# Car_cover_Main1.net
KiCad netlist of a schematic drawn in EAGLE
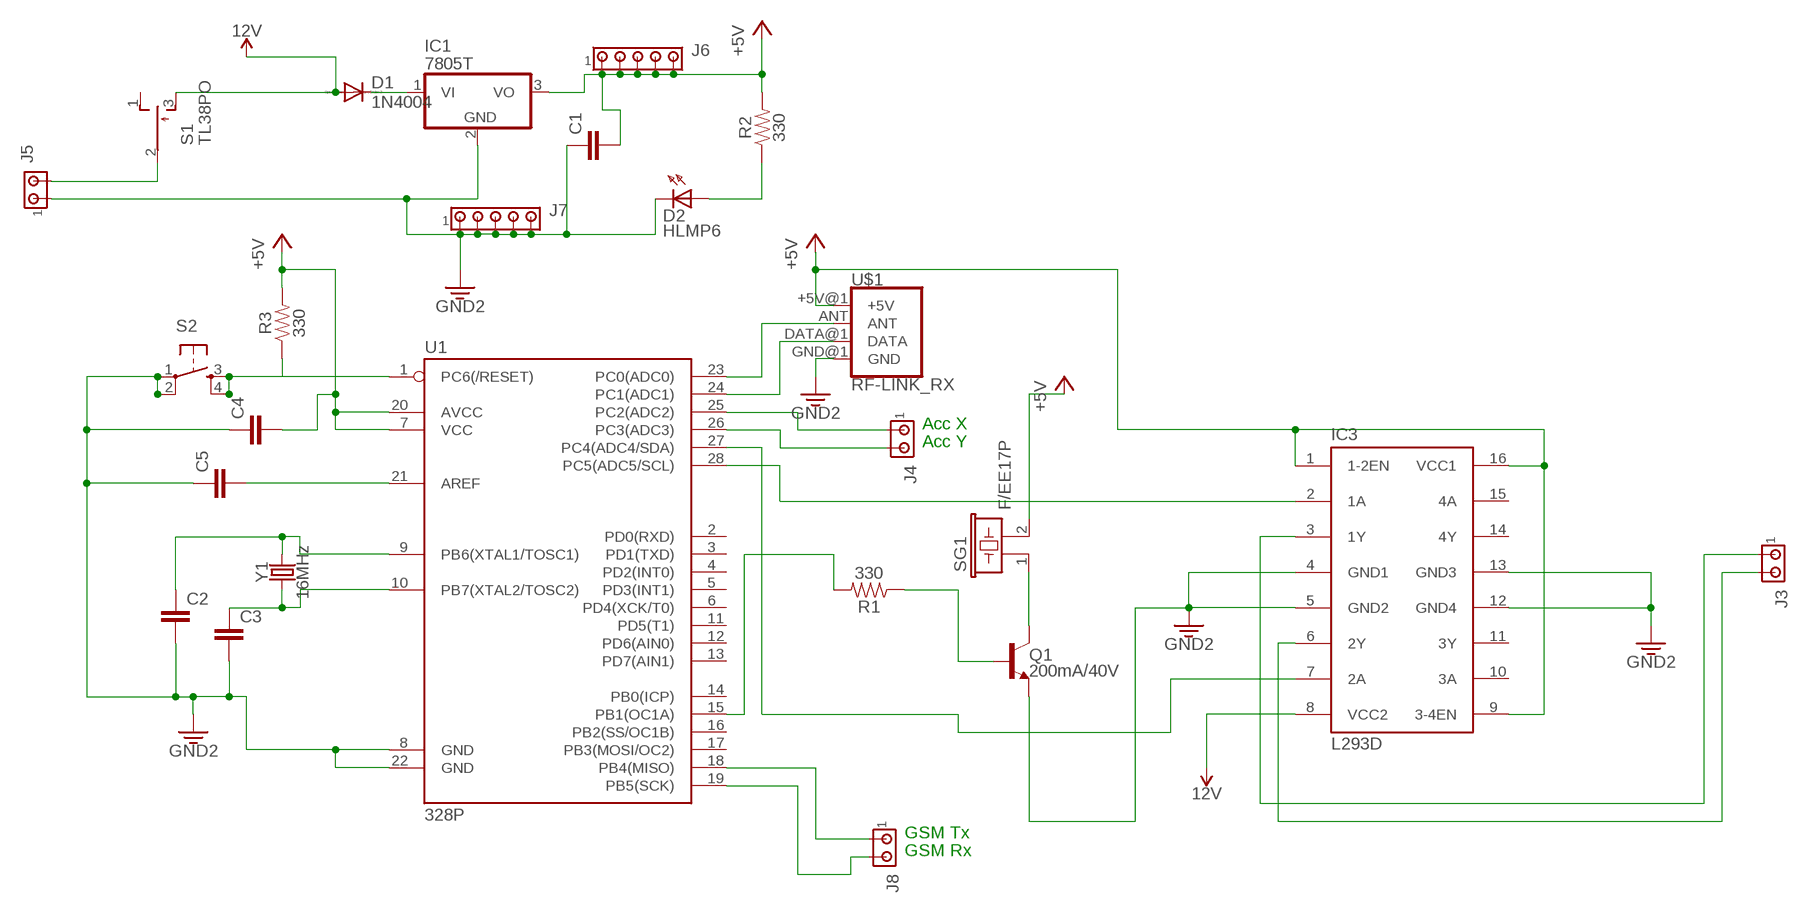
[diagram p0: schematic, sheet 1]

(export (version "E")
  (design (tool "Eeschema 10.0.6"))
  (components
    (comp (ref "C1")
      (value "C5/2.5")
      (footprint "eagle-import:C5B2.5")
      (libsource (lib "eagle-import") (part "C5/2.5"))
    )
    (comp (ref "C2")
      (value "C5/2.5")
      (footprint "eagle-import:C5B2.5")
      (libsource (lib "eagle-import") (part "C5/2.5"))
    )
    (comp (ref "C3")
      (value "C5/2.5")
      (footprint "eagle-import:C5B2.5")
      (libsource (lib "eagle-import") (part "C5/2.5"))
    )
    (comp (ref "C4")
      (value "C5/2.5")
      (footprint "eagle-import:C5B2.5")
      (libsource (lib "eagle-import") (part "C5/2.5"))
    )
    (comp (ref "C5")
      (value "C5/2.5")
      (footprint "eagle-import:C5B2.5")
      (libsource (lib "eagle-import") (part "C5/2.5"))
    )
    (comp (ref "D1")
      (value "1N4004")
      (footprint "eagle-import:DO41-10")
      (libsource (lib "eagle-import") (part "1N4004"))
    )
    (comp (ref "D2")
      (value "HLMP6")
      (footprint "eagle-import:HLMP6")
      (fields (field (name "MF") "AGILENT TECHNOLOGIES") (field (name "MPN") "HLMP-6500"))
      (libsource (lib "eagle-import") (part "HLMP6"))
    )
    (comp (ref "IC1")
      (value "7805T")
      (footprint "eagle-import:TO220H")
      (libsource (lib "eagle-import") (part "78T05"))
    )
    (comp (ref "IC3")
      (value "L293D")
      (footprint "eagle-import:DIL16")
      (libsource (lib "eagle-import") (part "L293D"))
    )
    (comp (ref "J3")
      (value "MTA02-156")
      (footprint "eagle-import:1X2MTA")
      (libsource (lib "eagle-import") (part "MTA02-156"))
    )
    (comp (ref "J4")
      (value "MTA02-156")
      (footprint "eagle-import:1X2MTA")
      (libsource (lib "eagle-import") (part "MTA02-156"))
    )
    (comp (ref "J5")
      (value "MTA02-156")
      (footprint "eagle-import:1X2MTA")
      (libsource (lib "eagle-import") (part "MTA02-156"))
    )
    (comp (ref "J6")
      (value "MTA05-100")
      (footprint "eagle-import:10X05MTA")
      (libsource (lib "eagle-import") (part "MTA05-100"))
    )
    (comp (ref "J7")
      (value "MTA05-100")
      (footprint "eagle-import:10X05MTA")
      (libsource (lib "eagle-import") (part "MTA05-100"))
    )
    (comp (ref "J8")
      (value "MTA02-156")
      (footprint "eagle-import:1X2MTA")
      (libsource (lib "eagle-import") (part "MTA02-156"))
    )
    (comp (ref "Q1")
      (value "200mA/40V")
      (footprint "eagle-import:TO-92")
      (libsource (lib "eagle-import") (part "TRANS_NPN-2N3904"))
    )
    (comp (ref "R1")
      (value "330")
      (footprint "eagle-import:AXIAL-0.3")
      (libsource (lib "eagle-import") (part "330OHM-HORIZ-1/10W-5%"))
    )
    (comp (ref "R2")
      (value "330")
      (footprint "eagle-import:AXIAL-0.3")
      (libsource (lib "eagle-import") (part "330OHM-HORIZ-1/10W-5%"))
    )
    (comp (ref "R3")
      (value "330")
      (footprint "eagle-import:AXIAL-0.3")
      (libsource (lib "eagle-import") (part "330OHM-HORIZ-1/10W-5%"))
    )
    (comp (ref "S1")
      (value "TL38PO")
      (footprint "eagle-import:TL3XPO")
      (libsource (lib "eagle-import") (part "TL38PO"))
    )
    (comp (ref "S2")
      (value "TAC_SWITCHPTH")
      (footprint "eagle-import:TACTILE-PTH")
      (libsource (lib "eagle-import") (part "TAC_SWITCHPTH"))
    )
    (comp (ref "SG1")
      (value "F/EE17P")
      (footprint "eagle-import:F_EE17P")
      (libsource (lib "eagle-import") (part "F/EE17P"))
    )
    (comp (ref "U$1")
      (value "RF-LINK_RX")
      (footprint "eagle-import:RF-LINK_RX")
      (libsource (lib "eagle-import") (part "RF-LINK_RX"))
    )
    (comp (ref "U1")
      (value "328P")
      (footprint "eagle-import:DIP28")
      (libsource (lib "eagle-import") (part "ATMEGA328P_PDIP"))
    )
    (comp (ref "Y1")
      (value "16MHz")
      (footprint "eagle-import:HC49US")
      (libsource (lib "eagle-import") (part "CRYSTAL-16MHZPTH-HC49US"))
    )
  )
  (nets
    (net (code "1") (name "+5V") (class "Default")
      (node (ref "C1") (pin "2") (pinfunction "2_2") (pintype "passive"))
      (node (ref "C4") (pin "2") (pinfunction "2_2") (pintype "passive"))
      (node (ref "IC1") (pin "3") (pinfunction "VO_3") (pintype "passive"))
      (node (ref "IC3") (pin "1") (pinfunction "1-2EN_1") (pintype "input"))
      (node (ref "IC3") (pin "16") (pinfunction "VCC1_16") (pintype "power_in"))
      (node (ref "IC3") (pin "9") (pinfunction "3-4EN_9") (pintype "input"))
      (node (ref "J6") (pin "1") (pinfunction "1_1") (pintype "passive"))
      (node (ref "J6") (pin "2") (pinfunction "2_2") (pintype "passive"))
      (node (ref "J6") (pin "3") (pinfunction "3_3") (pintype "passive"))
      (node (ref "J6") (pin "4") (pinfunction "4_4") (pintype "passive"))
      (node (ref "J6") (pin "5") (pinfunction "5_5") (pintype "passive"))
      (node (ref "R2") (pin "P$2") (pinfunction "2_P$2") (pintype "passive"))
      (node (ref "R3") (pin "P$2") (pinfunction "2_P$2") (pintype "passive"))
      (node (ref "SG1") (pin "2") (pinfunction "2_2") (pintype "passive"))
      (node (ref "U$1") (pin "+5V@1") (pinfunction "+5V_+5V@1") (pintype "power_in"))
      (node (ref "U1") (pin "20") (pinfunction "AVCC_20") (pintype "bidirectional"))
      (node (ref "U1") (pin "7") (pinfunction "VCC_7") (pintype "bidirectional"))
    )
    (net (code "2") (name "12V") (class "Default")
      (node (ref "D1") (pin "A") (pinfunction "A_A") (pintype "passive"))
      (node (ref "IC3") (pin "8") (pinfunction "VCC2_8") (pintype "power_in"))
      (node (ref "S1") (pin "3") (pinfunction "S_3") (pintype "passive"))
    )
    (net (code "3") (name "GND2") (class "Default")
      (node (ref "C1") (pin "1") (pinfunction "1_1") (pintype "passive"))
      (node (ref "C2") (pin "2") (pinfunction "2_2") (pintype "passive"))
      (node (ref "C3") (pin "2") (pinfunction "2_2") (pintype "passive"))
      (node (ref "C4") (pin "1") (pinfunction "1_1") (pintype "passive"))
      (node (ref "C5") (pin "1") (pinfunction "1_1") (pintype "passive"))
      (node (ref "D2") (pin "K") (pinfunction "K_K") (pintype "passive"))
      (node (ref "IC1") (pin "2") (pinfunction "GND_2") (pintype "passive"))
      (node (ref "IC3") (pin "12") (pinfunction "GND4_12") (pintype "power_in"))
      (node (ref "IC3") (pin "13") (pinfunction "GND3_13") (pintype "power_in"))
      (node (ref "IC3") (pin "4") (pinfunction "GND1_4") (pintype "power_in"))
      (node (ref "IC3") (pin "5") (pinfunction "GND2_5") (pintype "power_in"))
      (node (ref "J5") (pin "1") (pinfunction "1_1") (pintype "passive"))
      (node (ref "J7") (pin "1") (pinfunction "1_1") (pintype "passive"))
      (node (ref "J7") (pin "2") (pinfunction "2_2") (pintype "passive"))
      (node (ref "J7") (pin "3") (pinfunction "3_3") (pintype "passive"))
      (node (ref "J7") (pin "4") (pinfunction "4_4") (pintype "passive"))
      (node (ref "J7") (pin "5") (pinfunction "5_5") (pintype "passive"))
      (node (ref "Q1") (pin "1") (pinfunction "E_1") (pintype "passive"))
      (node (ref "S2") (pin "1") (pinfunction "1_1") (pintype "passive"))
      (node (ref "S2") (pin "2") (pinfunction "2_2") (pintype "passive"))
      (node (ref "U$1") (pin "GND@1") (pinfunction "GND_GND@1") (pintype "power_in"))
      (node (ref "U1") (pin "22") (pinfunction "GND_22") (pintype "bidirectional"))
      (node (ref "U1") (pin "8") (pinfunction "GND_8") (pintype "bidirectional"))
    )
    (net (code "4") (name "Net-(IC1-VI)") (class "Default")
      (node (ref "D1") (pin "C") (pinfunction "C_C") (pintype "passive"))
      (node (ref "IC1") (pin "1") (pinfunction "VI_1") (pintype "input"))
    )
    (net (code "5") (name "Net-(IC3-1A)") (class "Default")
      (node (ref "IC3") (pin "2") (pinfunction "1A_2") (pintype "input"))
      (node (ref "U1") (pin "28") (pinfunction "PC5(ADC5/SCL)_28") (pintype "bidirectional"))
    )
    (net (code "6") (name "Net-(IC3-1Y)") (class "Default")
      (node (ref "IC3") (pin "3") (pinfunction "1Y_3") (pintype "output"))
      (node (ref "J3") (pin "1") (pinfunction "1_1") (pintype "passive"))
    )
    (net (code "7") (name "Net-(IC3-2A)") (class "Default")
      (node (ref "IC3") (pin "7") (pinfunction "2A_7") (pintype "input"))
      (node (ref "U1") (pin "27") (pinfunction "PC4(ADC4/SDA)_27") (pintype "bidirectional"))
    )
    (net (code "8") (name "Net-(IC3-2Y)") (class "Default")
      (node (ref "IC3") (pin "6") (pinfunction "2Y_6") (pintype "output"))
      (node (ref "J3") (pin "2") (pinfunction "2_2") (pintype "passive"))
    )
    (net (code "9") (name "Net-(Q1-B)") (class "Default")
      (node (ref "Q1") (pin "2") (pinfunction "B_2") (pintype "passive"))
      (node (ref "R1") (pin "P$1") (pinfunction "1_P$1") (pintype "passive"))
    )
    (net (code "10") (name "Net-(Q1-C)") (class "Default")
      (node (ref "Q1") (pin "3") (pinfunction "C_3") (pintype "passive"))
      (node (ref "SG1") (pin "1") (pinfunction "1_1") (pintype "passive"))
    )
    (net (code "11") (name "Net-(R1-2)") (class "Default")
      (node (ref "R1") (pin "P$2") (pinfunction "2_P$2") (pintype "passive"))
      (node (ref "U1") (pin "15") (pinfunction "PB1(OC1A)_15") (pintype "bidirectional"))
    )
    (net (code "12") (name "Net-(R2-1)") (class "Default")
      (node (ref "D2") (pin "A") (pinfunction "A_A") (pintype "passive"))
      (node (ref "R2") (pin "P$1") (pinfunction "1_P$1") (pintype "passive"))
    )
    (net (code "13") (name "Net-(R3-1)") (class "Default")
      (node (ref "R3") (pin "P$1") (pinfunction "1_P$1") (pintype "passive"))
      (node (ref "S2") (pin "3") (pinfunction "3_3") (pintype "passive"))
      (node (ref "S2") (pin "4") (pinfunction "4_4") (pintype "passive"))
      (node (ref "U1") (pin "1") (pinfunction "PC6(/RESET)_1") (pintype "bidirectional"))
    )
    (net (code "14") (name "Net-(S1-P)") (class "Default")
      (node (ref "J5") (pin "2") (pinfunction "2_2") (pintype "passive"))
      (node (ref "S1") (pin "2") (pinfunction "P_2") (pintype "passive"))
    )
    (net (code "15") (name "Net-(U$1-DATA)") (class "Default")
      (node (ref "U$1") (pin "DATA@1") (pinfunction "DATA_DATA@1") (pintype "input"))
      (node (ref "U1") (pin "24") (pinfunction "PC1(ADC1)_24") (pintype "bidirectional"))
    )
    (net (code "16") (name "Net-(U1-AREF)") (class "Default")
      (node (ref "C5") (pin "2") (pinfunction "2_2") (pintype "passive"))
      (node (ref "U1") (pin "21") (pinfunction "AREF_21") (pintype "bidirectional"))
    )
    (net (code "17") (name "Net-(U1-PB4(MISO))") (class "Default")
      (node (ref "J8") (pin "1") (pinfunction "1_1") (pintype "passive"))
      (node (ref "U1") (pin "18") (pinfunction "PB4(MISO)_18") (pintype "bidirectional"))
    )
    (net (code "18") (name "Net-(U1-PB5(SCK))") (class "Default")
      (node (ref "J8") (pin "2") (pinfunction "2_2") (pintype "passive"))
      (node (ref "U1") (pin "19") (pinfunction "PB5(SCK)_19") (pintype "bidirectional"))
    )
    (net (code "19") (name "Net-(U1-PB6(XTAL1{slash}TOSC1))") (class "Default")
      (node (ref "C2") (pin "1") (pinfunction "1_1") (pintype "passive"))
      (node (ref "U1") (pin "9") (pinfunction "PB6(XTAL1/TOSC1)_9") (pintype "bidirectional"))
      (node (ref "Y1") (pin "2") (pinfunction "2_2") (pintype "passive"))
    )
    (net (code "20") (name "Net-(U1-PB7(XTAL2{slash}TOSC2))") (class "Default")
      (node (ref "C3") (pin "1") (pinfunction "1_1") (pintype "passive"))
      (node (ref "U1") (pin "10") (pinfunction "PB7(XTAL2/TOSC2)_10") (pintype "bidirectional"))
      (node (ref "Y1") (pin "1") (pinfunction "1_1") (pintype "passive"))
    )
    (net (code "21") (name "Net-(U1-PC0(ADC0))") (class "Default")
      (node (ref "U$1") (pin "ANT") (pinfunction "ANT_ANT") (pintype "passive"))
      (node (ref "U1") (pin "23") (pinfunction "PC0(ADC0)_23") (pintype "bidirectional"))
    )
    (net (code "22") (name "Net-(U1-PC2(ADC2))") (class "Default")
      (node (ref "J4") (pin "1") (pinfunction "1_1") (pintype "passive"))
      (node (ref "U1") (pin "25") (pinfunction "PC2(ADC2)_25") (pintype "bidirectional"))
    )
    (net (code "23") (name "Net-(U1-PC3(ADC3))") (class "Default")
      (node (ref "J4") (pin "2") (pinfunction "2_2") (pintype "passive"))
      (node (ref "U1") (pin "26") (pinfunction "PC3(ADC3)_26") (pintype "bidirectional"))
    )
    (net (code "24") (name "unconnected-(IC3-3A-Pad10)") (class "Default")
      (node (ref "IC3") (pin "10") (pinfunction "3A_10") (pintype "input"))
    )
    (net (code "25") (name "unconnected-(IC3-3Y-Pad11)") (class "Default")
      (node (ref "IC3") (pin "11") (pinfunction "3Y_11") (pintype "output"))
    )
    (net (code "26") (name "unconnected-(IC3-4A-Pad15)") (class "Default")
      (node (ref "IC3") (pin "15") (pinfunction "4A_15") (pintype "input"))
    )
    (net (code "27") (name "unconnected-(IC3-4Y-Pad14)") (class "Default")
      (node (ref "IC3") (pin "14") (pinfunction "4Y_14") (pintype "output"))
    )
    (net (code "28") (name "unconnected-(S1-O-Pad1)") (class "Default")
      (node (ref "S1") (pin "1") (pinfunction "O_1") (pintype "passive"))
    )
    (net (code "29") (name "unconnected-(U1-PB0(ICP)-Pad14)") (class "Default")
      (node (ref "U1") (pin "14") (pinfunction "PB0(ICP)_14") (pintype "bidirectional"))
    )
    (net (code "30") (name "unconnected-(U1-PB2(SS{slash}OC1B)-Pad16)") (class "Default")
      (node (ref "U1") (pin "16") (pinfunction "PB2(SS/OC1B)_16") (pintype "bidirectional"))
    )
    (net (code "31") (name "unconnected-(U1-PB3(MOSI{slash}OC2)-Pad17)") (class "Default")
      (node (ref "U1") (pin "17") (pinfunction "PB3(MOSI/OC2)_17") (pintype "bidirectional"))
    )
    (net (code "32") (name "unconnected-(U1-PD0(RXD)-Pad2)") (class "Default")
      (node (ref "U1") (pin "2") (pinfunction "PD0(RXD)_2") (pintype "bidirectional"))
    )
    (net (code "33") (name "unconnected-(U1-PD1(TXD)-Pad3)") (class "Default")
      (node (ref "U1") (pin "3") (pinfunction "PD1(TXD)_3") (pintype "bidirectional"))
    )
    (net (code "34") (name "unconnected-(U1-PD2(INT0)-Pad4)") (class "Default")
      (node (ref "U1") (pin "4") (pinfunction "PD2(INT0)_4") (pintype "bidirectional"))
    )
    (net (code "35") (name "unconnected-(U1-PD3(INT1)-Pad5)") (class "Default")
      (node (ref "U1") (pin "5") (pinfunction "PD3(INT1)_5") (pintype "bidirectional"))
    )
    (net (code "36") (name "unconnected-(U1-PD4(XCK{slash}T0)-Pad6)") (class "Default")
      (node (ref "U1") (pin "6") (pinfunction "PD4(XCK/T0)_6") (pintype "bidirectional"))
    )
    (net (code "37") (name "unconnected-(U1-PD5(T1)-Pad11)") (class "Default")
      (node (ref "U1") (pin "11") (pinfunction "PD5(T1)_11") (pintype "bidirectional"))
    )
    (net (code "38") (name "unconnected-(U1-PD6(AIN0)-Pad12)") (class "Default")
      (node (ref "U1") (pin "12") (pinfunction "PD6(AIN0)_12") (pintype "bidirectional"))
    )
    (net (code "39") (name "unconnected-(U1-PD7(AIN1)-Pad13)") (class "Default")
      (node (ref "U1") (pin "13") (pinfunction "PD7(AIN1)_13") (pintype "bidirectional"))
    )
  )
)
